# Condor2a_Plugs_REV_C.net
KiCad netlist of a schematic drawn in Altium Designer
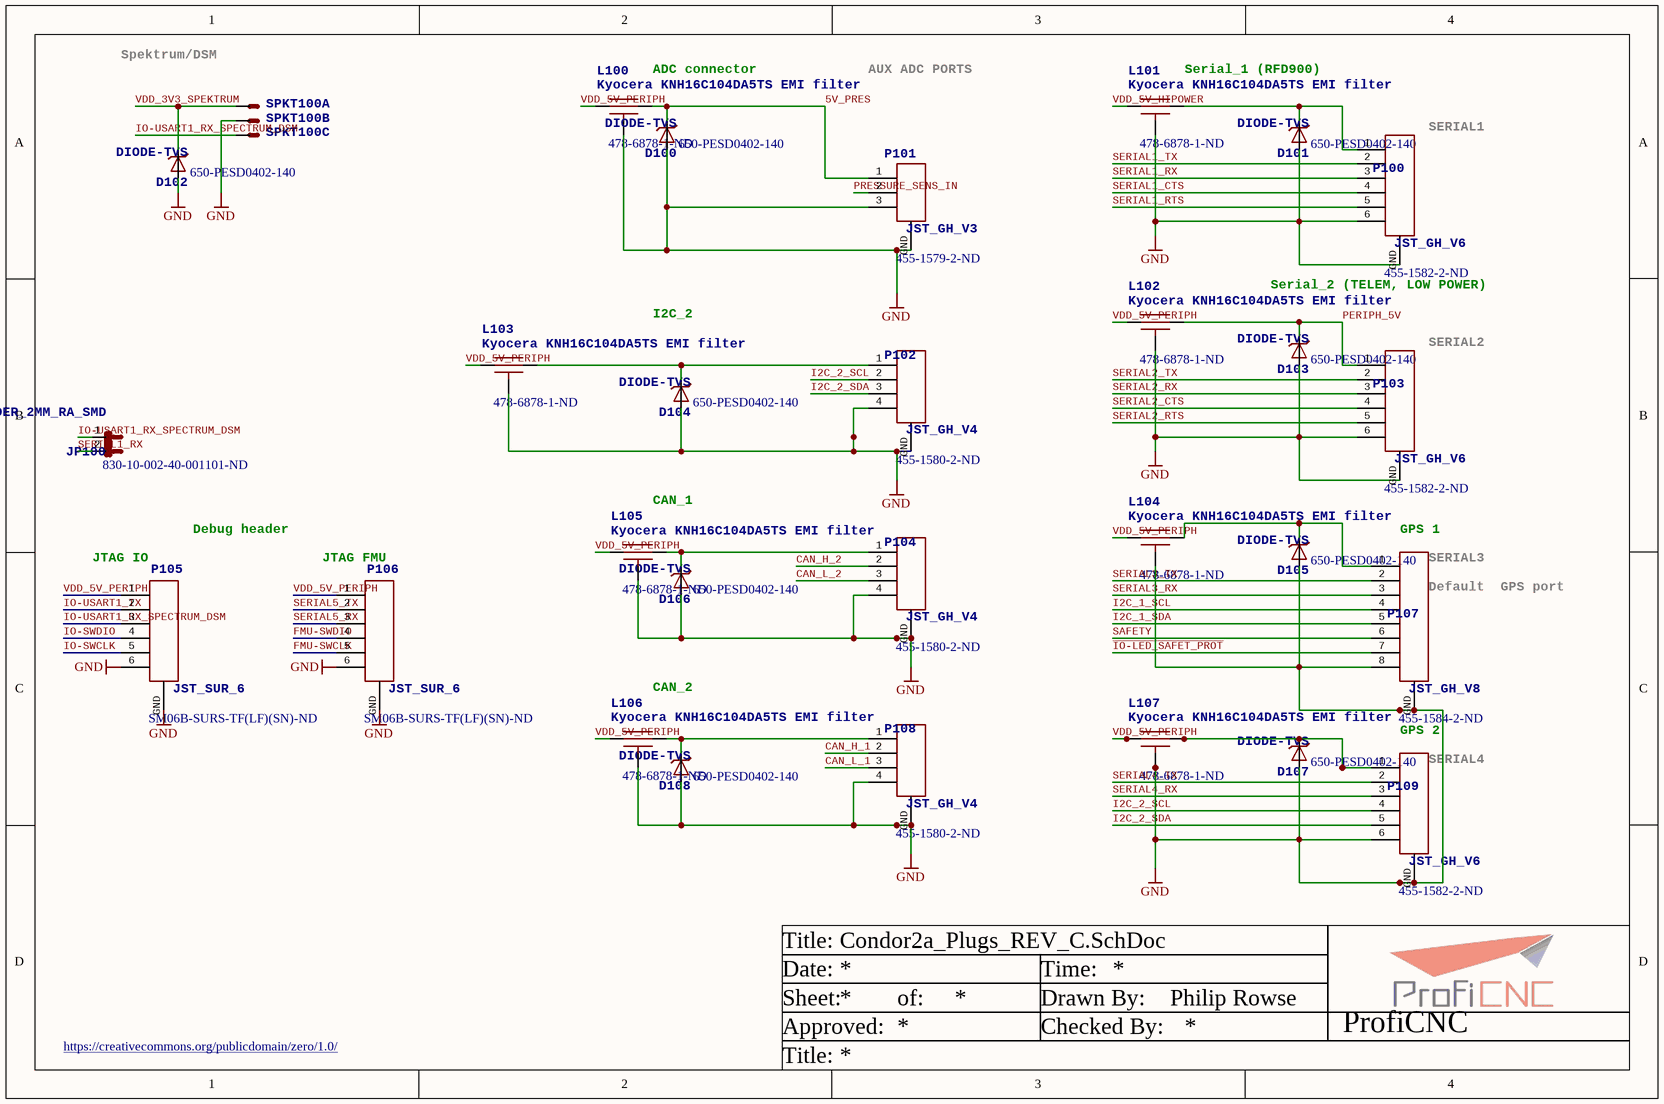
[diagram p0: Condor2a_Plugs_REV_C.SchDoc]

(export (version "E")
  (design (tool "Eeschema 10.0.6"))
  (components
    (comp (ref "D100")
      (value "DIODE-TVS")
      (footprint "0402-TVS")
      (description "Diode, TVS, 14VWM, 40VC, 0402, SMD")
      (fields (field (name "SUPPLIER PART NUMBER 1") "650-PESD0402-140"))
      (libsource (lib "CB_REV_C") (part "DIODE-TVS"))
    )
    (comp (ref "D101")
      (value "DIODE-TVS")
      (footprint "0402-TVS")
      (description "Diode, TVS, 14VWM, 40VC, 0402, SMD")
      (fields (field (name "SUPPLIER PART NUMBER 1") "650-PESD0402-140"))
      (libsource (lib "CB_REV_C") (part "DIODE-TVS"))
    )
    (comp (ref "D102")
      (value "DIODE-TVS")
      (footprint "0402-TVS")
      (description "Diode, TVS, 14VWM, 40VC, 0402, SMD")
      (fields (field (name "SUPPLIER PART NUMBER 1") "650-PESD0402-140"))
      (libsource (lib "CB_REV_C") (part "DIODE-TVS"))
    )
    (comp (ref "D103")
      (value "DIODE-TVS")
      (footprint "0402-TVS")
      (description "Diode, TVS, 14VWM, 40VC, 0402, SMD")
      (fields (field (name "SUPPLIER PART NUMBER 1") "650-PESD0402-140"))
      (libsource (lib "CB_REV_C") (part "DIODE-TVS"))
    )
    (comp (ref "D104")
      (value "DIODE-TVS")
      (footprint "0402-TVS")
      (description "Diode, TVS, 14VWM, 40VC, 0402, SMD")
      (fields (field (name "SUPPLIER PART NUMBER 1") "650-PESD0402-140"))
      (libsource (lib "CB_REV_C") (part "DIODE-TVS"))
    )
    (comp (ref "D105")
      (value "DIODE-TVS")
      (footprint "0402-TVS")
      (description "Diode, TVS, 14VWM, 40VC, 0402, SMD")
      (fields (field (name "SUPPLIER PART NUMBER 1") "650-PESD0402-140"))
      (libsource (lib "CB_REV_C") (part "DIODE-TVS"))
    )
    (comp (ref "D106")
      (value "DIODE-TVS")
      (footprint "0402-TVS")
      (description "Diode, TVS, 14VWM, 40VC, 0402, SMD")
      (fields (field (name "SUPPLIER PART NUMBER 1") "650-PESD0402-140"))
      (libsource (lib "CB_REV_C") (part "DIODE-TVS"))
    )
    (comp (ref "D107")
      (value "DIODE-TVS")
      (footprint "0402-TVS")
      (description "Diode, TVS, 14VWM, 40VC, 0402, SMD")
      (fields (field (name "SUPPLIER PART NUMBER 1") "650-PESD0402-140"))
      (libsource (lib "CB_REV_C") (part "DIODE-TVS"))
    )
    (comp (ref "D108")
      (value "DIODE-TVS")
      (footprint "0402-TVS")
      (description "Diode, TVS, 14VWM, 40VC, 0402, SMD")
      (fields (field (name "SUPPLIER PART NUMBER 1") "650-PESD0402-140"))
      (libsource (lib "CB_REV_C") (part "DIODE-TVS"))
    )
    (comp (ref "JP100")
      (value "HEADER_2MM_RA_SMD")
      (footprint "HEADER_2MM_RA_2")
      (description "Connector, PCB, 2MM, 2Pos, R/A, SMD, Au")
      (fields (field (name "SUPPLIER PART NUMBER 1") "830-10-002-40-001101-ND"))
      (libsource (lib "CB_REV_C") (part "HEADER_2MM_RA_SMD"))
    )
    (comp (ref "L100")
      (value "Kyocera KNH16C104DA5TS EMI filter")
      (footprint "KYOCERA-KNH16-DA")
      (description "Capacitor, Filter, 0.1uF, 25V, 2A, 0603, SMD")
      (fields (field (name "SUPPLIER PART NUMBER 1") "478-6878-1-ND"))
      (libsource (lib "CB_REV_C") (part "KNH16C104DA5TS"))
    )
    (comp (ref "L101")
      (value "Kyocera KNH16C104DA5TS EMI filter")
      (footprint "KYOCERA-KNH16-DA")
      (description "Capacitor, Filter, 0.1uF, 25V, 2A, 0603, SMD")
      (fields (field (name "SUPPLIER PART NUMBER 1") "478-6878-1-ND"))
      (libsource (lib "CB_REV_C") (part "KNH16C104DA5TS"))
    )
    (comp (ref "L102")
      (value "Kyocera KNH16C104DA5TS EMI filter")
      (footprint "KYOCERA-KNH16-DA")
      (description "Capacitor, Filter, 0.1uF, 25V, 2A, 0603, SMD")
      (fields (field (name "SUPPLIER PART NUMBER 1") "478-6878-1-ND"))
      (libsource (lib "CB_REV_C") (part "KNH16C104DA5TS"))
    )
    (comp (ref "L103")
      (value "Kyocera KNH16C104DA5TS EMI filter")
      (footprint "KYOCERA-KNH16-DA")
      (description "Capacitor, Filter, 0.1uF, 25V, 2A, 0603, SMD")
      (fields (field (name "SUPPLIER PART NUMBER 1") "478-6878-1-ND"))
      (libsource (lib "CB_REV_C") (part "KNH16C104DA5TS"))
    )
    (comp (ref "L104")
      (value "Kyocera KNH16C104DA5TS EMI filter")
      (footprint "KYOCERA-KNH16-DA")
      (description "Capacitor, Filter, 0.1uF, 25V, 2A, 0603, SMD")
      (fields (field (name "SUPPLIER PART NUMBER 1") "478-6878-1-ND"))
      (libsource (lib "CB_REV_C") (part "KNH16C104DA5TS"))
    )
    (comp (ref "L105")
      (value "Kyocera KNH16C104DA5TS EMI filter")
      (footprint "KYOCERA-KNH16-DA")
      (description "Capacitor, Filter, 0.1uF, 25V, 2A, 0603, SMD")
      (fields (field (name "SUPPLIER PART NUMBER 1") "478-6878-1-ND"))
      (libsource (lib "CB_REV_C") (part "KNH16C104DA5TS"))
    )
    (comp (ref "L106")
      (value "Kyocera KNH16C104DA5TS EMI filter")
      (footprint "KYOCERA-KNH16-DA")
      (description "Capacitor, Filter, 0.1uF, 25V, 2A, 0603, SMD")
      (fields (field (name "SUPPLIER PART NUMBER 1") "478-6878-1-ND"))
      (libsource (lib "CB_REV_C") (part "KNH16C104DA5TS"))
    )
    (comp (ref "L107")
      (value "Kyocera KNH16C104DA5TS EMI filter")
      (footprint "KYOCERA-KNH16-DA")
      (description "Capacitor, Filter, 0.1uF, 25V, 2A, 0603, SMD")
      (fields (field (name "SUPPLIER PART NUMBER 1") "478-6878-1-ND"))
      (libsource (lib "CB_REV_C") (part "KNH16C104DA5TS"))
    )
    (comp (ref "P100")
      (value "JST_GH_V6")
      (footprint "JST_GH_V6")
      (description "BM06B-GHS-TBT")
      (fields (field (name "SUPPLIER PART NUMBER 1") "455-1582-2-ND"))
      (libsource (lib "CB_REV_C") (part "JST_GH_V6"))
    )
    (comp (ref "P101")
      (value "JST_GH_V3")
      (footprint "JST_GH_V3")
      (description "BM03B-GHS-TBT")
      (fields (field (name "SUPPLIER PART NUMBER 1") "455-1579-2-ND"))
      (libsource (lib "CB_REV_C") (part "JST_GH_V3"))
    )
    (comp (ref "P102")
      (value "JST_GH_V4")
      (footprint "JST_GH_V4")
      (description "BM04B-GHS-TBT")
      (fields (field (name "SUPPLIER PART NUMBER 1") "455-1580-2-ND"))
      (libsource (lib "CB_REV_C") (part "JST_GH_V4"))
    )
    (comp (ref "P103")
      (value "JST_GH_V6")
      (footprint "JST_GH_V6")
      (description "BM06B-GHS-TBT")
      (fields (field (name "SUPPLIER PART NUMBER 1") "455-1582-2-ND"))
      (libsource (lib "CB_REV_C") (part "JST_GH_V6"))
    )
    (comp (ref "P104")
      (value "JST_GH_V4")
      (footprint "JST_GH_V4")
      (description "BM04B-GHS-TBT")
      (fields (field (name "SUPPLIER PART NUMBER 1") "455-1580-2-ND"))
      (libsource (lib "CB_REV_C") (part "JST_GH_V4"))
    )
    (comp (ref "P105")
      (value "JST_SUR_6")
      (footprint "JST_SUR_H6")
      (description "Connector, Header, 6Pos, .8mm IDC, R/A, SMD, Tin")
      (fields (field (name "SUPPLIER PART NUMBER 1") "SM06B-SURS-TF(LF)(SN)-ND"))
      (libsource (lib "CB_REV_C") (part "JST_SUR_6"))
    )
    (comp (ref "P106")
      (value "JST_SUR_6")
      (footprint "JST_SUR_H6")
      (description "Connector, Header, 6Pos, .8mm IDC, R/A, SMD, Tin")
      (fields (field (name "SUPPLIER PART NUMBER 1") "SM06B-SURS-TF(LF)(SN)-ND"))
      (libsource (lib "CB_REV_C") (part "JST_SUR_6"))
    )
    (comp (ref "P107")
      (value "JST_GH_V8")
      (footprint "JST_GH_V8")
      (description "BM08B-GHS-TBT")
      (fields (field (name "SUPPLIER PART NUMBER 1") "455-1584-2-ND"))
      (libsource (lib "CB_REV_C") (part "JST_GH_V8"))
    )
    (comp (ref "P108")
      (value "JST_GH_V4")
      (footprint "JST_GH_V4")
      (description "BM04B-GHS-TBT")
      (fields (field (name "SUPPLIER PART NUMBER 1") "455-1580-2-ND"))
      (libsource (lib "CB_REV_C") (part "JST_GH_V4"))
    )
    (comp (ref "P109")
      (value "JST_GH_V6")
      (footprint "JST_GH_V6")
      (description "BM06B-GHS-TBT")
      (fields (field (name "SUPPLIER PART NUMBER 1") "455-1582-2-ND"))
      (libsource (lib "CB_REV_C") (part "JST_GH_V6"))
    )
    (comp (ref "SPKT100")
      (value "CONN_SPEKTRUM_RX-TH")
      (footprint "B3B-ZR")
      (description "Spektrum RX connector; JST ZH series S3B-ZR-SM4A-TF")
      (fields (field (name "PARTNO") "B3B-ZR(LF)(SN)"))
      (libsource (lib "CB_REV_C") (part "CONN_SPEKTRUM_RX-TH"))
    )
  )
  (nets
    (net (code "1") (name "/5V_PRES") (class "Default")
      (node (ref "D100") (pin "C") (pinfunction "C_C") (pintype "passive"))
      (node (ref "L100") (pin "P$2") (pinfunction "P$2_P$2") (pintype "passive"))
      (node (ref "P101") (pin "1") (pinfunction "1_1") (pintype "passive"))
    )
    (net (code "2") (name "/CAN_H_1") (class "Default")
      (node (ref "P108") (pin "2") (pinfunction "2_2") (pintype "passive"))
    )
    (net (code "3") (name "/CAN_H_2") (class "Default")
      (node (ref "P104") (pin "2") (pinfunction "2_2") (pintype "passive"))
    )
    (net (code "4") (name "/CAN_L_1") (class "Default")
      (node (ref "P108") (pin "3") (pinfunction "3_3") (pintype "passive"))
    )
    (net (code "5") (name "/CAN_L_2") (class "Default")
      (node (ref "P104") (pin "3") (pinfunction "3_3") (pintype "passive"))
    )
    (net (code "6") (name "/FMU-SWCLK") (class "Default")
      (node (ref "P106") (pin "5") (pinfunction "5_5") (pintype "passive"))
    )
    (net (code "7") (name "/FMU-SWDIO") (class "Default")
      (node (ref "P106") (pin "4") (pinfunction "4_4") (pintype "passive"))
    )
    (net (code "8") (name "/I2C_1_SCL") (class "Default")
      (node (ref "P107") (pin "4") (pinfunction "4_4") (pintype "passive"))
    )
    (net (code "9") (name "/I2C_1_SDA") (class "Default")
      (node (ref "P107") (pin "5") (pinfunction "5_5") (pintype "passive"))
    )
    (net (code "10") (name "/I2C_2_SCL") (class "Default")
      (node (ref "P102") (pin "2") (pinfunction "2_2") (pintype "passive"))
      (node (ref "P109") (pin "4") (pinfunction "4_4") (pintype "passive"))
    )
    (net (code "11") (name "/I2C_2_SDA") (class "Default")
      (node (ref "P102") (pin "3") (pinfunction "3_3") (pintype "passive"))
      (node (ref "P109") (pin "5") (pinfunction "5_5") (pintype "passive"))
    )
    (net (code "12") (name "/IO-SWCLK") (class "Default")
      (node (ref "P105") (pin "5") (pinfunction "5_5") (pintype "passive"))
    )
    (net (code "13") (name "/IO-SWDIO") (class "Default")
      (node (ref "P105") (pin "4") (pinfunction "4_4") (pintype "passive"))
    )
    (net (code "14") (name "/IO-USART1_RX_SPECTRUM_DSM") (class "Default")
      (node (ref "JP100") (pin "1") (pinfunction "1_1") (pintype "passive"))
      (node (ref "P105") (pin "3") (pinfunction "3_3") (pintype "passive"))
      (node (ref "SPKT100") (pin "1") (pinfunction "S_1") (pintype "passive"))
    )
    (net (code "15") (name "/IO-USART1_TX") (class "Default")
      (node (ref "P105") (pin "2") (pinfunction "2_2") (pintype "passive"))
    )
    (net (code "16") (name "/PERIPH_5V") (class "Default")
      (node (ref "D103") (pin "C") (pinfunction "C_C") (pintype "passive"))
      (node (ref "L102") (pin "P$2") (pinfunction "P$2_P$2") (pintype "passive"))
      (node (ref "P103") (pin "1") (pinfunction "1_1") (pintype "passive"))
    )
    (net (code "17") (name "/PRESSURE_SENS_IN") (class "Default")
      (node (ref "P101") (pin "2") (pinfunction "2_2") (pintype "passive"))
    )
    (net (code "18") (name "/SAFETY") (class "Default")
      (node (ref "P107") (pin "6") (pinfunction "6_6") (pintype "passive"))
    )
    (net (code "19") (name "/SERIAL1_CTS") (class "Default")
      (node (ref "P100") (pin "4") (pinfunction "4_4") (pintype "passive"))
    )
    (net (code "20") (name "/SERIAL1_RTS") (class "Default")
      (node (ref "P100") (pin "5") (pinfunction "5_5") (pintype "passive"))
    )
    (net (code "21") (name "/SERIAL1_RX") (class "Default")
      (node (ref "JP100") (pin "2") (pinfunction "2_2") (pintype "passive"))
      (node (ref "P100") (pin "3") (pinfunction "3_3") (pintype "passive"))
    )
    (net (code "22") (name "/SERIAL1_TX") (class "Default")
      (node (ref "P100") (pin "2") (pinfunction "2_2") (pintype "passive"))
    )
    (net (code "23") (name "/SERIAL2_CTS") (class "Default")
      (node (ref "P103") (pin "4") (pinfunction "4_4") (pintype "passive"))
    )
    (net (code "24") (name "/SERIAL2_RTS") (class "Default")
      (node (ref "P103") (pin "5") (pinfunction "5_5") (pintype "passive"))
    )
    (net (code "25") (name "/SERIAL2_RX") (class "Default")
      (node (ref "P103") (pin "3") (pinfunction "3_3") (pintype "passive"))
    )
    (net (code "26") (name "/SERIAL2_TX") (class "Default")
      (node (ref "P103") (pin "2") (pinfunction "2_2") (pintype "passive"))
    )
    (net (code "27") (name "/SERIAL3_RX") (class "Default")
      (node (ref "P107") (pin "3") (pinfunction "3_3") (pintype "passive"))
    )
    (net (code "28") (name "/SERIAL3_TX") (class "Default")
      (node (ref "P107") (pin "2") (pinfunction "2_2") (pintype "passive"))
    )
    (net (code "29") (name "/SERIAL4_RX") (class "Default")
      (node (ref "P109") (pin "3") (pinfunction "3_3") (pintype "passive"))
    )
    (net (code "30") (name "/SERIAL4_TX") (class "Default")
      (node (ref "P109") (pin "2") (pinfunction "2_2") (pintype "passive"))
    )
    (net (code "31") (name "/SERIAL5_RX") (class "Default")
      (node (ref "P106") (pin "3") (pinfunction "3_3") (pintype "passive"))
    )
    (net (code "32") (name "/SERIAL5_TX") (class "Default")
      (node (ref "P106") (pin "2") (pinfunction "2_2") (pintype "passive"))
    )
    (net (code "33") (name "/VDD_3V3_SPEKTRUM") (class "Default")
      (node (ref "D102") (pin "C") (pinfunction "C_C") (pintype "passive"))
      (node (ref "SPKT100") (pin "3") (pinfunction "S_3") (pintype "passive"))
    )
    (net (code "34") (name "/VDD_5V_HIPOWER") (class "Default")
      (node (ref "L101") (pin "P$1") (pinfunction "P$1_P$1") (pintype "passive"))
    )
    (net (code "35") (name "/VDD_5V_PERIPH") (class "Default")
      (node (ref "L100") (pin "P$1") (pinfunction "P$1_P$1") (pintype "passive"))
      (node (ref "L102") (pin "P$1") (pinfunction "P$1_P$1") (pintype "passive"))
      (node (ref "L103") (pin "P$1") (pinfunction "P$1_P$1") (pintype "passive"))
      (node (ref "L104") (pin "P$1") (pinfunction "P$1_P$1") (pintype "passive"))
      (node (ref "L105") (pin "P$1") (pinfunction "P$1_P$1") (pintype "passive"))
      (node (ref "L106") (pin "P$1") (pinfunction "P$1_P$1") (pintype "passive"))
      (node (ref "L107") (pin "P$1") (pinfunction "P$1_P$1") (pintype "passive"))
      (node (ref "P105") (pin "1") (pinfunction "1_1") (pintype "passive"))
      (node (ref "P106") (pin "1") (pinfunction "1_1") (pintype "passive"))
    )
    (net (code "36") (name "/~{IO-LED_SAFET_PROT}") (class "Default")
      (node (ref "P107") (pin "7") (pinfunction "7_7") (pintype "passive"))
    )
    (net (code "37") (name "GND") (class "Default")
      (node (ref "D100") (pin "A") (pinfunction "A_A") (pintype "passive"))
      (node (ref "D101") (pin "A") (pinfunction "A_A") (pintype "passive"))
      (node (ref "D102") (pin "A") (pinfunction "A_A") (pintype "passive"))
      (node (ref "D103") (pin "A") (pinfunction "A_A") (pintype "passive"))
      (node (ref "D104") (pin "A") (pinfunction "A_A") (pintype "passive"))
      (node (ref "D105") (pin "A") (pinfunction "A_A") (pintype "passive"))
      (node (ref "D106") (pin "A") (pinfunction "A_A") (pintype "passive"))
      (node (ref "D107") (pin "A") (pinfunction "A_A") (pintype "passive"))
      (node (ref "D108") (pin "A") (pinfunction "A_A") (pintype "passive"))
      (node (ref "L100") (pin "GND") (pinfunction "GND_GND") (pintype "passive"))
      (node (ref "L101") (pin "GND") (pinfunction "GND_GND") (pintype "passive"))
      (node (ref "L102") (pin "GND") (pinfunction "GND_GND") (pintype "passive"))
      (node (ref "L103") (pin "GND") (pinfunction "GND_GND") (pintype "passive"))
      (node (ref "L104") (pin "GND") (pinfunction "GND_GND") (pintype "passive"))
      (node (ref "L105") (pin "GND") (pinfunction "GND_GND") (pintype "passive"))
      (node (ref "L106") (pin "GND") (pinfunction "GND_GND") (pintype "passive"))
      (node (ref "L107") (pin "GND") (pinfunction "GND_GND") (pintype "passive"))
      (node (ref "P100") (pin "6") (pinfunction "6_6") (pintype "passive"))
      (node (ref "P100") (pin "GND") (pinfunction "GND_GND") (pintype "passive"))
      (node (ref "P101") (pin "3") (pinfunction "3_3") (pintype "passive"))
      (node (ref "P101") (pin "GND") (pinfunction "GND_GND") (pintype "passive"))
      (node (ref "P102") (pin "4") (pinfunction "4_4") (pintype "passive"))
      (node (ref "P102") (pin "GND") (pinfunction "GND_GND") (pintype "passive"))
      (node (ref "P103") (pin "6") (pinfunction "6_6") (pintype "passive"))
      (node (ref "P103") (pin "GND") (pinfunction "GND_GND") (pintype "passive"))
      (node (ref "P104") (pin "4") (pinfunction "4_4") (pintype "passive"))
      (node (ref "P104") (pin "GND") (pinfunction "GND_GND") (pintype "passive"))
      (node (ref "P105") (pin "6") (pinfunction "6_6") (pintype "passive"))
      (node (ref "P105") (pin "GND") (pinfunction "GND_GND") (pintype "passive"))
      (node (ref "P106") (pin "6") (pinfunction "6_6") (pintype "passive"))
      (node (ref "P106") (pin "GND") (pinfunction "GND_GND") (pintype "passive"))
      (node (ref "P107") (pin "8") (pinfunction "8_8") (pintype "passive"))
      (node (ref "P107") (pin "GND") (pinfunction "GND_GND") (pintype "passive"))
      (node (ref "P108") (pin "4") (pinfunction "4_4") (pintype "passive"))
      (node (ref "P108") (pin "GND") (pinfunction "GND_GND") (pintype "passive"))
      (node (ref "P109") (pin "6") (pinfunction "6_6") (pintype "passive"))
      (node (ref "P109") (pin "GND") (pinfunction "GND_GND") (pintype "passive"))
      (node (ref "SPKT100") (pin "2") (pinfunction "S_2") (pintype "passive"))
    )
    (net (code "38") (name "Net-(D101-PadC)") (class "Default")
      (node (ref "D101") (pin "C") (pinfunction "C_C") (pintype "passive"))
      (node (ref "L101") (pin "P$2") (pinfunction "P$2_P$2") (pintype "passive"))
      (node (ref "P100") (pin "1") (pinfunction "1_1") (pintype "passive"))
    )
    (net (code "39") (name "Net-(D104-PadC)") (class "Default")
      (node (ref "D104") (pin "C") (pinfunction "C_C") (pintype "passive"))
      (node (ref "L103") (pin "P$2") (pinfunction "P$2_P$2") (pintype "passive"))
      (node (ref "P102") (pin "1") (pinfunction "1_1") (pintype "passive"))
    )
    (net (code "40") (name "Net-(D105-PadC)") (class "Default")
      (node (ref "D105") (pin "C") (pinfunction "C_C") (pintype "passive"))
      (node (ref "L104") (pin "P$2") (pinfunction "P$2_P$2") (pintype "passive"))
      (node (ref "P107") (pin "1") (pinfunction "1_1") (pintype "passive"))
    )
    (net (code "41") (name "Net-(D106-PadC)") (class "Default")
      (node (ref "D106") (pin "C") (pinfunction "C_C") (pintype "passive"))
      (node (ref "L105") (pin "P$2") (pinfunction "P$2_P$2") (pintype "passive"))
      (node (ref "P104") (pin "1") (pinfunction "1_1") (pintype "passive"))
    )
    (net (code "42") (name "Net-(D107-PadC)") (class "Default")
      (node (ref "D107") (pin "C") (pinfunction "C_C") (pintype "passive"))
      (node (ref "L107") (pin "P$2") (pinfunction "P$2_P$2") (pintype "passive"))
      (node (ref "P109") (pin "1") (pinfunction "1_1") (pintype "passive"))
    )
    (net (code "43") (name "Net-(D108-PadC)") (class "Default")
      (node (ref "D108") (pin "C") (pinfunction "C_C") (pintype "passive"))
      (node (ref "L106") (pin "P$2") (pinfunction "P$2_P$2") (pintype "passive"))
      (node (ref "P108") (pin "1") (pinfunction "1_1") (pintype "passive"))
    )
  )
)
